# HR2M.net
KiCad netlist of a schematic drawn in EAGLE
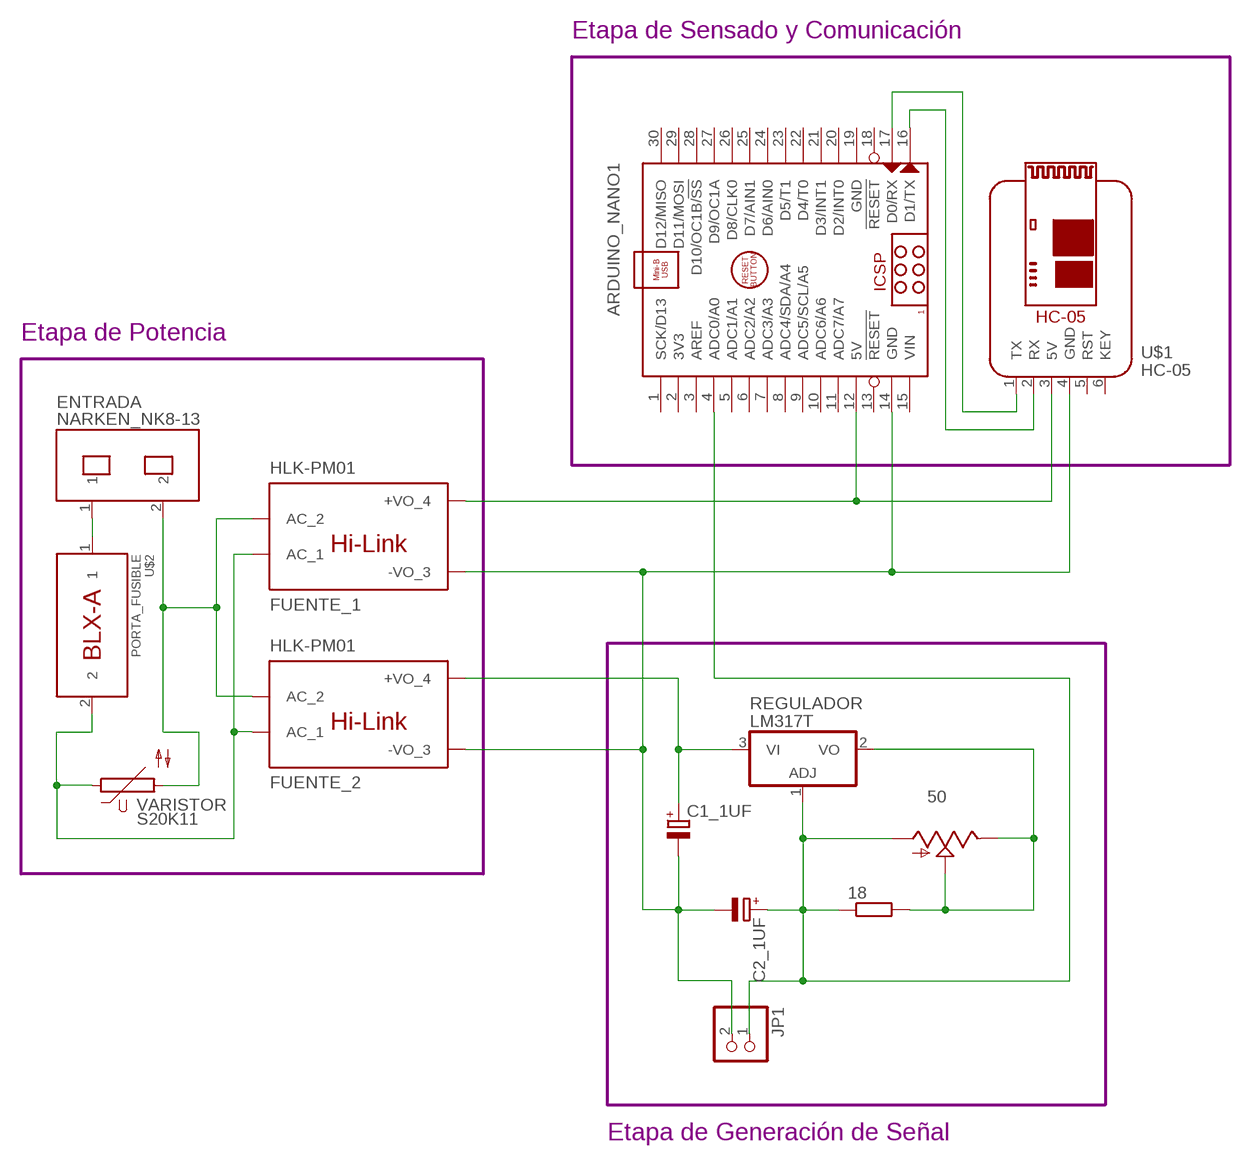
[diagram p0: schematic, sheet 1]

(export (version "E")
  (design (tool "Eeschema 10.0.6"))
  (components
    (comp (ref "18")
      (value "R-EU_0207/12")
      (footprint "eagle-import:0207_12")
      (libsource (lib "eagle-import") (part "R-EU_0207/12"))
    )
    (comp (ref "50")
      (value "TRIM_US-B64Y")
      (footprint "eagle-import:B64Y")
      (libsource (lib "eagle-import") (part "TRIM_US-B64Y"))
    )
    (comp (ref "ARDUINO_NANO1")
      (value "ARDUINO_NANO")
      (footprint "eagle-import:ARDUINO_NANO")
      (libsource (lib "eagle-import") (part "ARDUINO_NANO"))
    )
    (comp (ref "C1_1UF")
      (value "CPOL-EUE2.5-6")
      (footprint "eagle-import:E2,5-6")
      (libsource (lib "eagle-import") (part "CPOL-EUE2.5-6"))
    )
    (comp (ref "C2_1UF")
      (value "CPOL-EUE2.5-6")
      (footprint "eagle-import:E2,5-6")
      (libsource (lib "eagle-import") (part "CPOL-EUE2.5-6"))
    )
    (comp (ref "ENTRADA")
      (value "NARKEN_NK8-13")
      (footprint "eagle-import:NARKEN_NK8-13")
      (fields (field (name "VOLTAGE") "250V"))
      (libsource (lib "eagle-import") (part "NARKEN_NK8-13"))
    )
    (comp (ref "FUENTE_1")
      (value "HLK-PM01")
      (footprint "eagle-import:HLK-PM01")
      (libsource (lib "eagle-import") (part "HLK-PM01"))
    )
    (comp (ref "FUENTE_2")
      (value "HLK-PM01")
      (footprint "eagle-import:HLK-PM01")
      (libsource (lib "eagle-import") (part "HLK-PM01"))
    )
    (comp (ref "JP1")
      (value "PINHD-1X2")
      (footprint "eagle-import:1X02")
      (libsource (lib "eagle-import") (part "PINHD-1X2"))
    )
    (comp (ref "REGULADOR")
      (value "LM317T")
      (footprint "eagle-import:TO220V")
      (libsource (lib "eagle-import") (part "LM317T"))
    )
    (comp (ref "U$1")
      (value "HC-05")
      (footprint "eagle-import:HC-0X_V")
      (libsource (lib "eagle-import") (part "HC-05"))
    )
    (comp (ref "U$2")
      (value "PORTA_FUSIBLE")
      (footprint "eagle-import:PORTA_FUSIBLE")
      (libsource (lib "eagle-import") (part "PORTA_FUSIBLE"))
    )
    (comp (ref "VARISTOR")
      (value "S20K11")
      (footprint "eagle-import:S20K11")
      (libsource (lib "eagle-import") (part "S20K11"))
    )
  )
  (nets
    (net (code "1") (name "/GND") (class "Default")
      (node (ref "ARDUINO_NANO1") (pin "19") (pinfunction "GND_19") (pintype "power_in"))
    )
    (net (code "2") (name "/VIN") (class "Default")
      (node (ref "ARDUINO_NANO1") (pin "15") (pinfunction "VIN_15") (pintype "power_in"))
    )
    (net (code "3") (name "Net-(ARDUINO_NANO1-5V)") (class "Default")
      (node (ref "ARDUINO_NANO1") (pin "12") (pinfunction "5V_12") (pintype "power_in"))
      (node (ref "FUENTE_1") (pin "+VO_4") (pinfunction "+VO_4_+VO_4") (pintype "output"))
      (node (ref "U$1") (pin "3") (pinfunction "5V_3") (pintype "power_in"))
    )
    (net (code "4") (name "Net-(ARDUINO_NANO1-ADC0{slash}A0)") (class "Default")
      (node (ref "18") (pin "1") (pinfunction "1_1") (pintype "passive"))
      (node (ref "50") (pin "A") (pinfunction "A_A") (pintype "passive"))
      (node (ref "ARDUINO_NANO1") (pin "4") (pinfunction "ADC0/A0_4") (pintype "bidirectional"))
      (node (ref "C2_1UF") (pin "+") (pinfunction "+_+") (pintype "passive"))
      (node (ref "JP1") (pin "1") (pinfunction "1_1") (pintype "passive"))
      (node (ref "REGULADOR") (pin "1") (pinfunction "ADJ_1") (pintype "input"))
    )
    (net (code "5") (name "Net-(ARDUINO_NANO1-D0{slash}RX)") (class "Default")
      (node (ref "ARDUINO_NANO1") (pin "17") (pinfunction "D0/RX_17") (pintype "bidirectional"))
      (node (ref "U$1") (pin "1") (pinfunction "TX_1") (pintype "output"))
    )
    (net (code "6") (name "Net-(ARDUINO_NANO1-D1{slash}TX)") (class "Default")
      (node (ref "ARDUINO_NANO1") (pin "16") (pinfunction "D1/TX_16") (pintype "bidirectional"))
      (node (ref "U$1") (pin "2") (pinfunction "RX_2") (pintype "input"))
    )
    (net (code "7") (name "Net-(ENTRADA-Pad1)") (class "Default")
      (node (ref "ENTRADA") (pin "1") (pinfunction "1_1") (pintype "bidirectional"))
      (node (ref "U$2") (pin "1") (pinfunction "1_1") (pintype "bidirectional"))
    )
    (net (code "8") (name "Net-(ENTRADA-Pad2)") (class "Default")
      (node (ref "ENTRADA") (pin "2") (pinfunction "2_2") (pintype "bidirectional"))
      (node (ref "FUENTE_1") (pin "AC_2") (pinfunction "AC_2_AC_2") (pintype "input"))
      (node (ref "FUENTE_2") (pin "AC_2") (pinfunction "AC_2_AC_2") (pintype "input"))
      (node (ref "VARISTOR") (pin "2") (pinfunction "2_2") (pintype "passive"))
    )
    (net (code "9") (name "Net-(FUENTE_1-PadAC_1)") (class "Default")
      (node (ref "FUENTE_1") (pin "AC_1") (pinfunction "AC_1_AC_1") (pintype "input"))
      (node (ref "FUENTE_2") (pin "AC_1") (pinfunction "AC_1_AC_1") (pintype "input"))
      (node (ref "U$2") (pin "2") (pinfunction "2_2") (pintype "bidirectional"))
      (node (ref "VARISTOR") (pin "1") (pinfunction "1_1") (pintype "passive"))
    )
    (net (code "10") (name "Net-(REGULADOR-VI)") (class "Default")
      (node (ref "C1_1UF") (pin "+") (pinfunction "+_+") (pintype "passive"))
      (node (ref "FUENTE_2") (pin "+VO_4") (pinfunction "+VO_4_+VO_4") (pintype "output"))
      (node (ref "REGULADOR") (pin "3") (pinfunction "VI_3") (pintype "input"))
    )
    (net (code "11") (name "Net-(REGULADOR-VO)") (class "Default")
      (node (ref "18") (pin "2") (pinfunction "2_2") (pintype "passive"))
      (node (ref "50") (pin "E") (pinfunction "E_E") (pintype "passive"))
      (node (ref "50") (pin "S") (pinfunction "S_S") (pintype "passive"))
      (node (ref "REGULADOR") (pin "2") (pinfunction "VO_2") (pintype "passive"))
    )
    (net (code "12") (name "Net-(U$1-GND)") (class "Default")
      (node (ref "ARDUINO_NANO1") (pin "14") (pinfunction "GND_14") (pintype "power_in"))
      (node (ref "C1_1UF") (pin "-") (pinfunction "-_-") (pintype "passive"))
      (node (ref "C2_1UF") (pin "-") (pinfunction "-_-") (pintype "passive"))
      (node (ref "FUENTE_1") (pin "-VO_3") (pinfunction "-VO_3_-VO_3") (pintype "output"))
      (node (ref "FUENTE_2") (pin "-VO_3") (pinfunction "-VO_3_-VO_3") (pintype "output"))
      (node (ref "JP1") (pin "2") (pinfunction "2_2") (pintype "passive"))
      (node (ref "U$1") (pin "4") (pinfunction "GND_4") (pintype "power_in"))
    )
    (net (code "13") (name "unconnected-(ARDUINO_NANO1-3V3-Pad2)") (class "Default")
      (node (ref "ARDUINO_NANO1") (pin "2") (pinfunction "3V3_2") (pintype "output"))
    )
    (net (code "14") (name "unconnected-(ARDUINO_NANO1-ADC1{slash}A1-Pad5)") (class "Default")
      (node (ref "ARDUINO_NANO1") (pin "5") (pinfunction "ADC1/A1_5") (pintype "bidirectional"))
    )
    (net (code "15") (name "unconnected-(ARDUINO_NANO1-ADC2{slash}A2-Pad6)") (class "Default")
      (node (ref "ARDUINO_NANO1") (pin "6") (pinfunction "ADC2/A2_6") (pintype "bidirectional"))
    )
    (net (code "16") (name "unconnected-(ARDUINO_NANO1-ADC3{slash}A3-Pad7)") (class "Default")
      (node (ref "ARDUINO_NANO1") (pin "7") (pinfunction "ADC3/A3_7") (pintype "bidirectional"))
    )
    (net (code "17") (name "unconnected-(ARDUINO_NANO1-ADC4{slash}SDA{slash}A4-Pad8)") (class "Default")
      (node (ref "ARDUINO_NANO1") (pin "8") (pinfunction "ADC4/SDA/A4_8") (pintype "bidirectional"))
    )
    (net (code "18") (name "unconnected-(ARDUINO_NANO1-ADC5{slash}SCL{slash}A5-Pad9)") (class "Default")
      (node (ref "ARDUINO_NANO1") (pin "9") (pinfunction "ADC5/SCL/A5_9") (pintype "bidirectional"))
    )
    (net (code "19") (name "unconnected-(ARDUINO_NANO1-ADC6{slash}A6-Pad10)") (class "Default")
      (node (ref "ARDUINO_NANO1") (pin "10") (pinfunction "ADC6/A6_10") (pintype "bidirectional"))
    )
    (net (code "20") (name "unconnected-(ARDUINO_NANO1-ADC7{slash}A7-Pad11)") (class "Default")
      (node (ref "ARDUINO_NANO1") (pin "11") (pinfunction "ADC7/A7_11") (pintype "bidirectional"))
    )
    (net (code "21") (name "unconnected-(ARDUINO_NANO1-AREF-Pad3)") (class "Default")
      (node (ref "ARDUINO_NANO1") (pin "3") (pinfunction "AREF_3") (pintype "input"))
    )
    (net (code "22") (name "unconnected-(ARDUINO_NANO1-D2{slash}INT0-Pad20)") (class "Default")
      (node (ref "ARDUINO_NANO1") (pin "20") (pinfunction "D2/INT0_20") (pintype "bidirectional"))
    )
    (net (code "23") (name "unconnected-(ARDUINO_NANO1-D3{slash}INT1-Pad21)") (class "Default")
      (node (ref "ARDUINO_NANO1") (pin "21") (pinfunction "D3/INT1_21") (pintype "bidirectional"))
    )
    (net (code "24") (name "unconnected-(ARDUINO_NANO1-D4{slash}T0-Pad22)") (class "Default")
      (node (ref "ARDUINO_NANO1") (pin "22") (pinfunction "D4/T0_22") (pintype "bidirectional"))
    )
    (net (code "25") (name "unconnected-(ARDUINO_NANO1-D5{slash}T1-Pad23)") (class "Default")
      (node (ref "ARDUINO_NANO1") (pin "23") (pinfunction "D5/T1_23") (pintype "bidirectional"))
    )
    (net (code "26") (name "unconnected-(ARDUINO_NANO1-D6{slash}AIN0-Pad24)") (class "Default")
      (node (ref "ARDUINO_NANO1") (pin "24") (pinfunction "D6/AIN0_24") (pintype "bidirectional"))
    )
    (net (code "27") (name "unconnected-(ARDUINO_NANO1-D7{slash}AIN1-Pad25)") (class "Default")
      (node (ref "ARDUINO_NANO1") (pin "25") (pinfunction "D7/AIN1_25") (pintype "bidirectional"))
    )
    (net (code "28") (name "unconnected-(ARDUINO_NANO1-D8{slash}CLK0-Pad26)") (class "Default")
      (node (ref "ARDUINO_NANO1") (pin "26") (pinfunction "D8/CLK0_26") (pintype "bidirectional"))
    )
    (net (code "29") (name "unconnected-(ARDUINO_NANO1-D9{slash}OC1A-Pad27)") (class "Default")
      (node (ref "ARDUINO_NANO1") (pin "27") (pinfunction "D9/OC1A_27") (pintype "bidirectional"))
    )
    (net (code "30") (name "unconnected-(ARDUINO_NANO1-D10{slash}OC1B{slash}~{SS}-Pad28)") (class "Default")
      (node (ref "ARDUINO_NANO1") (pin "28") (pinfunction "D10/OC1B/~{SS}_28") (pintype "bidirectional"))
    )
    (net (code "31") (name "unconnected-(ARDUINO_NANO1-D11{slash}MOSI-Pad29)") (class "Default")
      (node (ref "ARDUINO_NANO1") (pin "29") (pinfunction "D11/MOSI_29") (pintype "bidirectional"))
    )
    (net (code "32") (name "unconnected-(ARDUINO_NANO1-D12{slash}MISO-Pad30)") (class "Default")
      (node (ref "ARDUINO_NANO1") (pin "30") (pinfunction "D12/MISO_30") (pintype "bidirectional"))
    )
    (net (code "33") (name "unconnected-(ARDUINO_NANO1-SCK{slash}D13-Pad1)") (class "Default")
      (node (ref "ARDUINO_NANO1") (pin "1") (pinfunction "SCK/D13_1") (pintype "bidirectional"))
    )
    (net (code "34") (name "unconnected-(ARDUINO_NANO1-~{RESET}-Pad13)") (class "Default")
      (node (ref "ARDUINO_NANO1") (pin "13") (pinfunction "~{RESET}_13") (pintype "input"))
    )
    (net (code "35") (name "unconnected-(ARDUINO_NANO1-~{RESET}-Pad18)") (class "Default")
      (node (ref "ARDUINO_NANO1") (pin "18") (pinfunction "~{RESET}_18") (pintype "input"))
    )
    (net (code "36") (name "unconnected-(U$1-KEY-Pad6)") (class "Default")
      (node (ref "U$1") (pin "6") (pinfunction "KEY_6") (pintype "bidirectional"))
    )
    (net (code "37") (name "unconnected-(U$1-RST-Pad5)") (class "Default")
      (node (ref "U$1") (pin "5") (pinfunction "RST_5") (pintype "bidirectional"))
    )
  )
)
